# amiga_external_floppy_adapter_rev2_1.net
KiCad netlist of a schematic drawn in EAGLE
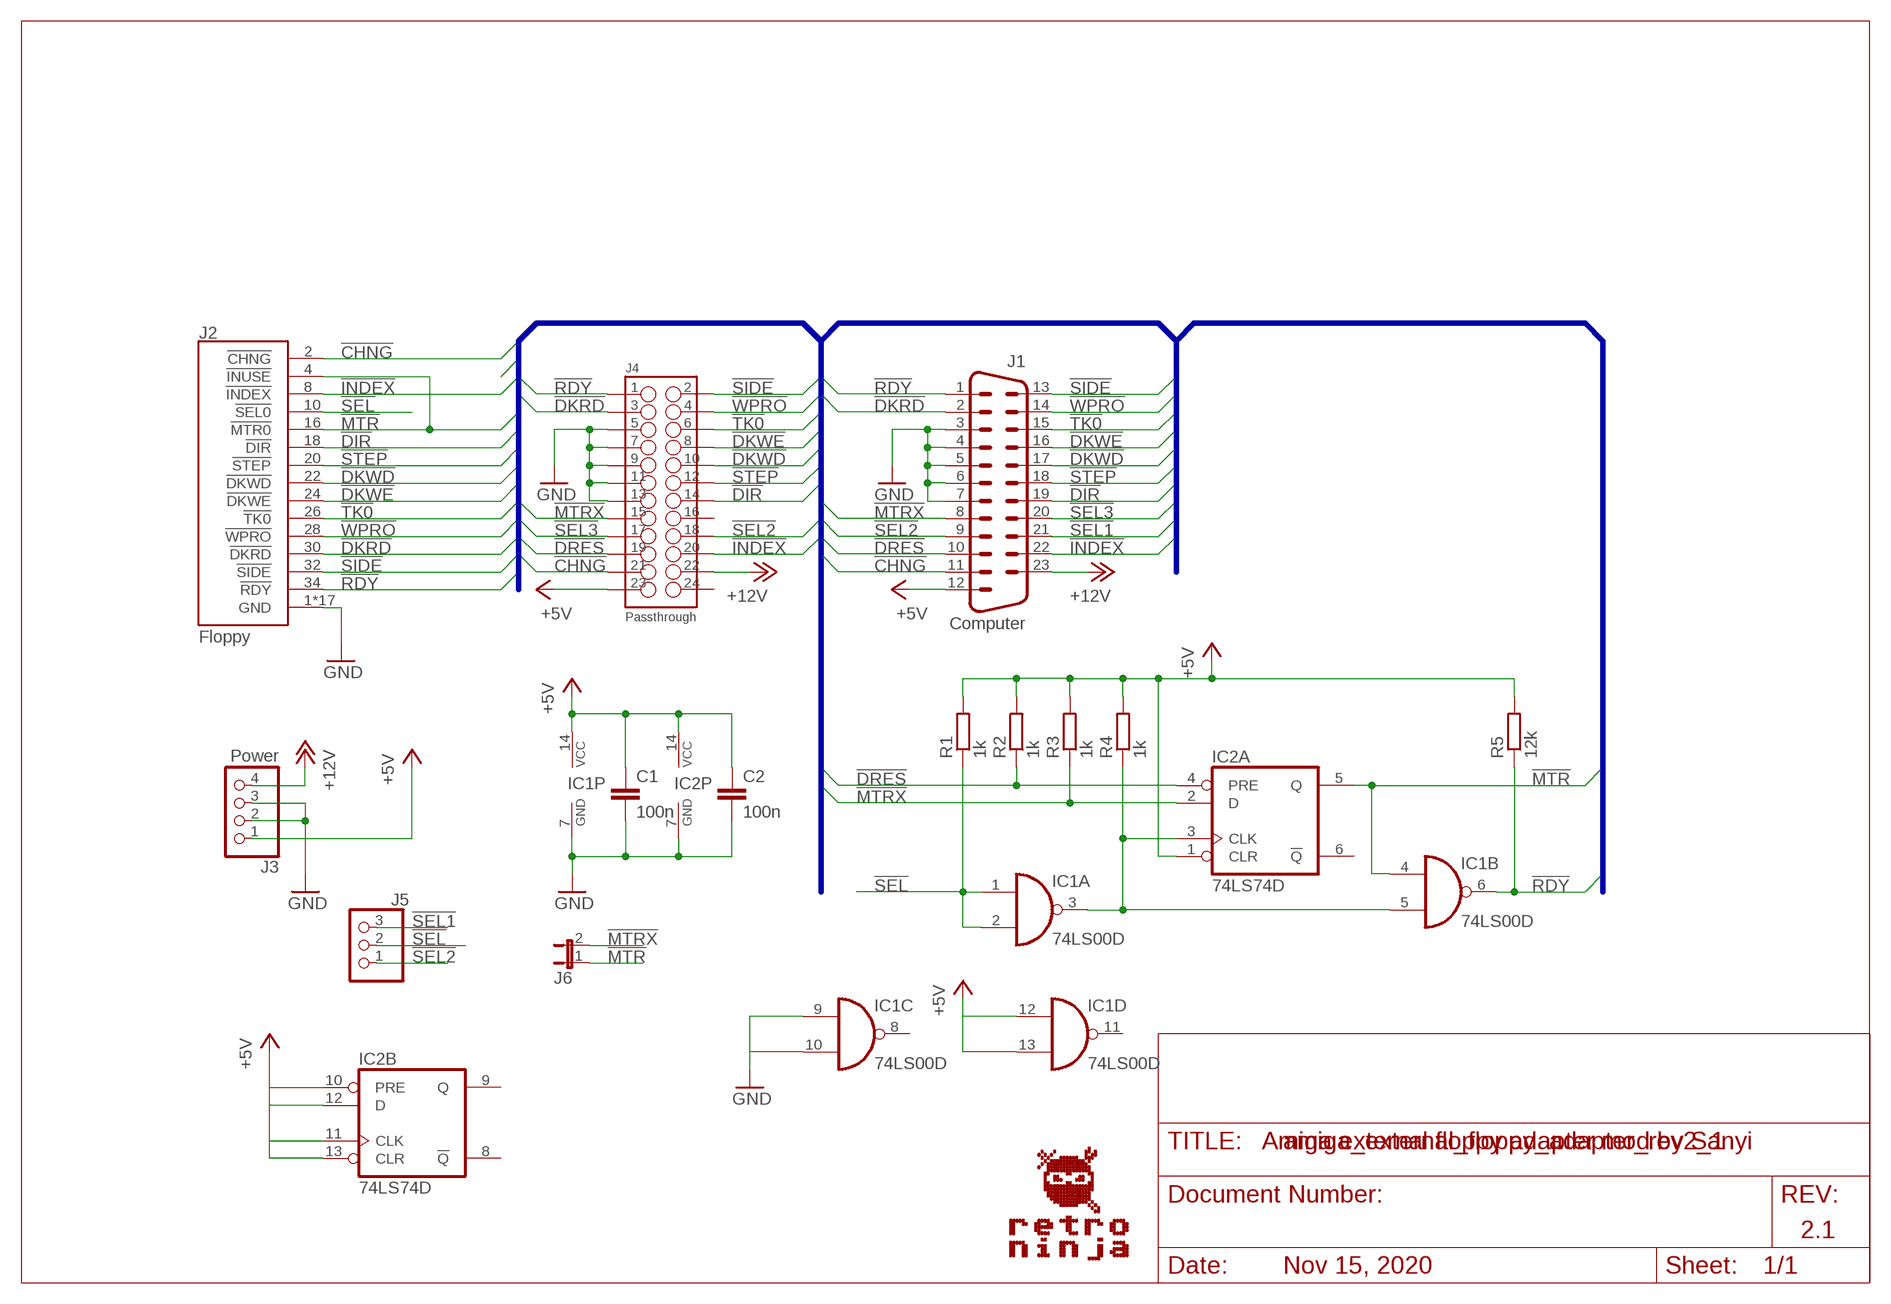
[diagram p0: schematic, sheet 1]

(export (version "E")
  (design (tool "Eeschema 10.0.6"))
  (components
    (comp (ref "C1")
      (value "100n")
      (footprint "eagle-import:C1206")
      (libsource (lib "eagle-import") (part "C-EUC1206"))
    )
    (comp (ref "C2")
      (value "100n")
      (footprint "eagle-import:C1206")
      (libsource (lib "eagle-import") (part "C-EUC1206"))
    )
    (comp (ref "IC1")
      (value "74LS00D")
      (footprint "eagle-import:SO14")
      (libsource (lib "eagle-import") (part "7400DLS"))
    )
    (comp (ref "IC2")
      (value "74LS74D")
      (footprint "eagle-import:SO14")
      (libsource (lib "eagle-import") (part "7474DLS"))
    )
    (comp (ref "J1")
      (value "Computer")
      (footprint "eagle-import:DSUB_M23D")
      (libsource (lib "eagle-import") (part "DSUB_M23"))
    )
    (comp (ref "J2")
      (value "Floppy")
      (footprint "eagle-import:HEADER_2X17_WALLED")
      (libsource (lib "eagle-import") (part "AMIGA_FLOPPYDRV_CONNECTOR/IDC"))
    )
    (comp (ref "J3")
      (value "Power")
      (footprint "eagle-import:1X04")
      (libsource (lib "eagle-import") (part "PINHD-1X4"))
    )
    (comp (ref "J4")
      (value "Passthrough")
      (footprint "eagle-import:HEADER_2X12_WALLED")
      (libsource (lib "eagle-import") (part "HEADER_2X12/IDC"))
    )
    (comp (ref "J5")
      (value "PINHD-1X3")
      (footprint "eagle-import:1X03")
      (libsource (lib "eagle-import") (part "PINHD-1X3"))
    )
    (comp (ref "J6")
      (value "JP1E")
      (footprint "eagle-import:JP1")
      (libsource (lib "eagle-import") (part "JP1E"))
    )
    (comp (ref "R1")
      (value "1k")
      (footprint "eagle-import:R1206")
      (libsource (lib "eagle-import") (part "R-EU_R1206"))
    )
    (comp (ref "R2")
      (value "1k")
      (footprint "eagle-import:R1206")
      (libsource (lib "eagle-import") (part "R-EU_R1206"))
    )
    (comp (ref "R3")
      (value "1k")
      (footprint "eagle-import:R1206")
      (libsource (lib "eagle-import") (part "R-EU_R1206"))
    )
    (comp (ref "R4")
      (value "1k")
      (footprint "eagle-import:R1206")
      (libsource (lib "eagle-import") (part "R-EU_R1206"))
    )
    (comp (ref "R5")
      (value "12k")
      (footprint "eagle-import:R1206")
      (libsource (lib "eagle-import") (part "R-EU_R1206"))
    )
  )
  (nets
    (net (code "1") (name "+5V") (class "Default")
      (node (ref "C1") (pin "1") (pinfunction "1_1") (pintype "passive"))
      (node (ref "C2") (pin "1") (pinfunction "1_1") (pintype "passive"))
      (node (ref "IC1") (pin "12") (pinfunction "I0_12") (pintype "input"))
      (node (ref "IC1") (pin "13") (pinfunction "I1_13") (pintype "input"))
      (node (ref "IC1") (pin "14") (pinfunction "VCC_14") (pintype "power_in"))
      (node (ref "IC2") (pin "1") (pinfunction "CLR_1") (pintype "input"))
      (node (ref "IC2") (pin "10") (pinfunction "PRE_10") (pintype "input"))
      (node (ref "IC2") (pin "11") (pinfunction "CLK_11") (pintype "input"))
      (node (ref "IC2") (pin "12") (pinfunction "D_12") (pintype "input"))
      (node (ref "IC2") (pin "13") (pinfunction "CLR_13") (pintype "input"))
      (node (ref "IC2") (pin "14") (pinfunction "VCC_14") (pintype "power_in"))
      (node (ref "J1") (pin "12") (pinfunction "12_12") (pintype "passive"))
      (node (ref "J3") (pin "1") (pinfunction "1_1") (pintype "passive"))
      (node (ref "J4") (pin "23") (pinfunction "23_23") (pintype "bidirectional"))
      (node (ref "R1") (pin "2") (pinfunction "2_2") (pintype "passive"))
      (node (ref "R2") (pin "2") (pinfunction "2_2") (pintype "passive"))
      (node (ref "R3") (pin "2") (pinfunction "2_2") (pintype "passive"))
      (node (ref "R4") (pin "2") (pinfunction "2_2") (pintype "passive"))
      (node (ref "R5") (pin "2") (pinfunction "2_2") (pintype "passive"))
    )
    (net (code "2") (name "+12V") (class "Default")
      (node (ref "J1") (pin "23") (pinfunction "23_23") (pintype "passive"))
      (node (ref "J3") (pin "4") (pinfunction "4_4") (pintype "passive"))
      (node (ref "J4") (pin "22") (pinfunction "22_22") (pintype "bidirectional"))
    )
    (net (code "3") (name "/~{CHNG}") (class "Default")
      (node (ref "J1") (pin "11") (pinfunction "11_11") (pintype "passive"))
      (node (ref "J2") (pin "2") (pinfunction "~{CHNG}_2") (pintype "bidirectional"))
      (node (ref "J4") (pin "21") (pinfunction "21_21") (pintype "bidirectional"))
    )
    (net (code "4") (name "/~{DIR}") (class "Default")
      (node (ref "J1") (pin "19") (pinfunction "19_19") (pintype "passive"))
      (node (ref "J2") (pin "18") (pinfunction "~{DIR}_18") (pintype "bidirectional"))
      (node (ref "J4") (pin "14") (pinfunction "14_14") (pintype "bidirectional"))
    )
    (net (code "5") (name "/~{DKRD}") (class "Default")
      (node (ref "J1") (pin "2") (pinfunction "2_2") (pintype "passive"))
      (node (ref "J2") (pin "30") (pinfunction "~{DKRD}_30") (pintype "bidirectional"))
      (node (ref "J4") (pin "3") (pinfunction "3_3") (pintype "bidirectional"))
    )
    (net (code "6") (name "/~{DKWD}") (class "Default")
      (node (ref "J1") (pin "17") (pinfunction "17_17") (pintype "passive"))
      (node (ref "J2") (pin "22") (pinfunction "~{DKWD}_22") (pintype "bidirectional"))
      (node (ref "J4") (pin "10") (pinfunction "10_10") (pintype "bidirectional"))
    )
    (net (code "7") (name "/~{DKWE}") (class "Default")
      (node (ref "J1") (pin "16") (pinfunction "16_16") (pintype "passive"))
      (node (ref "J2") (pin "24") (pinfunction "~{DKWE}_24") (pintype "bidirectional"))
      (node (ref "J4") (pin "8") (pinfunction "8_8") (pintype "bidirectional"))
    )
    (net (code "8") (name "/~{DRES}") (class "Default")
      (node (ref "IC2") (pin "4") (pinfunction "PRE_4") (pintype "input"))
      (node (ref "J1") (pin "10") (pinfunction "10_10") (pintype "passive"))
      (node (ref "J4") (pin "19") (pinfunction "19_19") (pintype "bidirectional"))
      (node (ref "R2") (pin "1") (pinfunction "1_1") (pintype "passive"))
    )
    (net (code "9") (name "/~{INDEX}") (class "Default")
      (node (ref "J1") (pin "22") (pinfunction "22_22") (pintype "passive"))
      (node (ref "J2") (pin "8") (pinfunction "~{INDEX}_8") (pintype "bidirectional"))
      (node (ref "J4") (pin "20") (pinfunction "20_20") (pintype "bidirectional"))
    )
    (net (code "10") (name "/~{MTRX}") (class "Default")
      (node (ref "IC2") (pin "2") (pinfunction "D_2") (pintype "input"))
      (node (ref "J1") (pin "8") (pinfunction "8_8") (pintype "passive"))
      (node (ref "J4") (pin "15") (pinfunction "15_15") (pintype "bidirectional"))
      (node (ref "J6") (pin "2") (pinfunction "2_2") (pintype "passive"))
      (node (ref "R3") (pin "1") (pinfunction "1_1") (pintype "passive"))
    )
    (net (code "11") (name "/~{MTR}") (class "Default")
      (node (ref "IC1") (pin "4") (pinfunction "I0_4") (pintype "input"))
      (node (ref "IC2") (pin "5") (pinfunction "Q_5") (pintype "output"))
      (node (ref "J2") (pin "16") (pinfunction "~{MTR0}_16") (pintype "bidirectional"))
      (node (ref "J2") (pin "4") (pinfunction "~{INUSE}_4") (pintype "bidirectional"))
      (node (ref "J6") (pin "1") (pinfunction "1_1") (pintype "passive"))
    )
    (net (code "12") (name "/~{RDY}") (class "Default")
      (node (ref "IC1") (pin "6") (pinfunction "O_6") (pintype "output"))
      (node (ref "J1") (pin "1") (pinfunction "1_1") (pintype "passive"))
      (node (ref "J2") (pin "34") (pinfunction "~{RDY}_34") (pintype "bidirectional"))
      (node (ref "J4") (pin "1") (pinfunction "1_1") (pintype "bidirectional"))
      (node (ref "R5") (pin "1") (pinfunction "1_1") (pintype "passive"))
    )
    (net (code "13") (name "/~{SEL1}") (class "Default")
      (node (ref "J1") (pin "21") (pinfunction "21_21") (pintype "passive"))
      (node (ref "J5") (pin "3") (pinfunction "3_3") (pintype "passive"))
    )
    (net (code "14") (name "/~{SEL2}") (class "Default")
      (node (ref "J1") (pin "9") (pinfunction "9_9") (pintype "passive"))
      (node (ref "J4") (pin "18") (pinfunction "18_18") (pintype "bidirectional"))
      (node (ref "J5") (pin "1") (pinfunction "1_1") (pintype "passive"))
    )
    (net (code "15") (name "/~{SEL3}") (class "Default")
      (node (ref "J1") (pin "20") (pinfunction "20_20") (pintype "passive"))
      (node (ref "J4") (pin "17") (pinfunction "17_17") (pintype "bidirectional"))
    )
    (net (code "16") (name "/~{SEL}") (class "Default")
      (node (ref "IC1") (pin "1") (pinfunction "I0_1") (pintype "input"))
      (node (ref "IC1") (pin "2") (pinfunction "I1_2") (pintype "input"))
      (node (ref "J2") (pin "10") (pinfunction "~{SEL0}_10") (pintype "bidirectional"))
      (node (ref "J5") (pin "2") (pinfunction "2_2") (pintype "passive"))
      (node (ref "R1") (pin "1") (pinfunction "1_1") (pintype "passive"))
    )
    (net (code "17") (name "/~{SIDE}") (class "Default")
      (node (ref "J1") (pin "13") (pinfunction "13_13") (pintype "passive"))
      (node (ref "J2") (pin "32") (pinfunction "~{SIDE}_32") (pintype "bidirectional"))
      (node (ref "J4") (pin "2") (pinfunction "2_2") (pintype "bidirectional"))
    )
    (net (code "18") (name "/~{STEP}") (class "Default")
      (node (ref "J1") (pin "18") (pinfunction "18_18") (pintype "passive"))
      (node (ref "J2") (pin "20") (pinfunction "~{STEP}_20") (pintype "bidirectional"))
      (node (ref "J4") (pin "12") (pinfunction "12_12") (pintype "bidirectional"))
    )
    (net (code "19") (name "/~{TK0}") (class "Default")
      (node (ref "J1") (pin "15") (pinfunction "15_15") (pintype "passive"))
      (node (ref "J2") (pin "26") (pinfunction "~{TK0}_26") (pintype "bidirectional"))
      (node (ref "J4") (pin "6") (pinfunction "6_6") (pintype "bidirectional"))
    )
    (net (code "20") (name "/~{WPRO}") (class "Default")
      (node (ref "J1") (pin "14") (pinfunction "14_14") (pintype "passive"))
      (node (ref "J2") (pin "28") (pinfunction "~{WPRO}_28") (pintype "bidirectional"))
      (node (ref "J4") (pin "4") (pinfunction "4_4") (pintype "bidirectional"))
    )
    (net (code "21") (name "GND") (class "Default")
      (node (ref "C1") (pin "2") (pinfunction "2_2") (pintype "passive"))
      (node (ref "C2") (pin "2") (pinfunction "2_2") (pintype "passive"))
      (node (ref "IC1") (pin "10") (pinfunction "I1_10") (pintype "input"))
      (node (ref "IC1") (pin "7") (pinfunction "GND_7") (pintype "power_in"))
      (node (ref "IC1") (pin "9") (pinfunction "I0_9") (pintype "input"))
      (node (ref "IC2") (pin "7") (pinfunction "GND_7") (pintype "power_in"))
      (node (ref "J1") (pin "3") (pinfunction "3_3") (pintype "passive"))
      (node (ref "J1") (pin "4") (pinfunction "4_4") (pintype "passive"))
      (node (ref "J1") (pin "5") (pinfunction "5_5") (pintype "passive"))
      (node (ref "J1") (pin "6") (pinfunction "6_6") (pintype "passive"))
      (node (ref "J1") (pin "7") (pinfunction "7_7") (pintype "passive"))
      (node (ref "J2") (pin "1") (pinfunction "GND_1") (pintype "power_in"))
      (node (ref "J2") (pin "11") (pinfunction "GND_11") (pintype "power_in"))
      (node (ref "J2") (pin "13") (pinfunction "GND_13") (pintype "power_in"))
      (node (ref "J2") (pin "15") (pinfunction "GND_15") (pintype "power_in"))
      (node (ref "J2") (pin "17") (pinfunction "GND_17") (pintype "power_in"))
      (node (ref "J2") (pin "19") (pinfunction "GND_19") (pintype "power_in"))
      (node (ref "J2") (pin "21") (pinfunction "GND_21") (pintype "power_in"))
      (node (ref "J2") (pin "23") (pinfunction "GND_23") (pintype "power_in"))
      (node (ref "J2") (pin "25") (pinfunction "GND_25") (pintype "power_in"))
      (node (ref "J2") (pin "27") (pinfunction "GND_27") (pintype "power_in"))
      (node (ref "J2") (pin "29") (pinfunction "GND_29") (pintype "power_in"))
      (node (ref "J2") (pin "3") (pinfunction "GND_3") (pintype "power_in"))
      (node (ref "J2") (pin "31") (pinfunction "GND_31") (pintype "power_in"))
      (node (ref "J2") (pin "33") (pinfunction "GND_33") (pintype "power_in"))
      (node (ref "J2") (pin "5") (pinfunction "GND_5") (pintype "power_in"))
      (node (ref "J2") (pin "7") (pinfunction "GND_7") (pintype "power_in"))
      (node (ref "J2") (pin "9") (pinfunction "GND_9") (pintype "power_in"))
      (node (ref "J3") (pin "2") (pinfunction "2_2") (pintype "passive"))
      (node (ref "J3") (pin "3") (pinfunction "3_3") (pintype "passive"))
      (node (ref "J4") (pin "11") (pinfunction "11_11") (pintype "bidirectional"))
      (node (ref "J4") (pin "13") (pinfunction "13_13") (pintype "bidirectional"))
      (node (ref "J4") (pin "5") (pinfunction "5_5") (pintype "bidirectional"))
      (node (ref "J4") (pin "7") (pinfunction "7_7") (pintype "bidirectional"))
      (node (ref "J4") (pin "9") (pinfunction "9_9") (pintype "bidirectional"))
    )
    (net (code "22") (name "Net-(IC1A-O)") (class "Default")
      (node (ref "IC1") (pin "3") (pinfunction "O_3") (pintype "output"))
      (node (ref "IC1") (pin "5") (pinfunction "I1_5") (pintype "input"))
      (node (ref "IC2") (pin "3") (pinfunction "CLK_3") (pintype "input"))
      (node (ref "R4") (pin "1") (pinfunction "1_1") (pintype "passive"))
    )
    (net (code "23") (name "unconnected-(IC1C-O-Pad8)") (class "Default")
      (node (ref "IC1") (pin "8") (pinfunction "O_8") (pintype "output"))
    )
    (net (code "24") (name "unconnected-(IC1D-O-Pad11)") (class "Default")
      (node (ref "IC1") (pin "11") (pinfunction "O_11") (pintype "output"))
    )
    (net (code "25") (name "unconnected-(IC2A-~{Q}-Pad6)") (class "Default")
      (node (ref "IC2") (pin "6") (pinfunction "~{Q}_6") (pintype "output"))
    )
    (net (code "26") (name "unconnected-(IC2B-Q-Pad9)") (class "Default")
      (node (ref "IC2") (pin "9") (pinfunction "Q_9") (pintype "output"))
    )
    (net (code "27") (name "unconnected-(IC2B-~{Q}-Pad8)") (class "Default")
      (node (ref "IC2") (pin "8") (pinfunction "~{Q}_8") (pintype "output"))
    )
    (net (code "28") (name "unconnected-(J4-Pad16)") (class "Default")
      (node (ref "J4") (pin "16") (pinfunction "16_16") (pintype "bidirectional"))
    )
    (net (code "29") (name "unconnected-(J4-Pad24)") (class "Default")
      (node (ref "J4") (pin "24") (pinfunction "24_24") (pintype "bidirectional"))
    )
  )
)
